# Slave.net
KiCad netlist of a schematic drawn in EAGLE
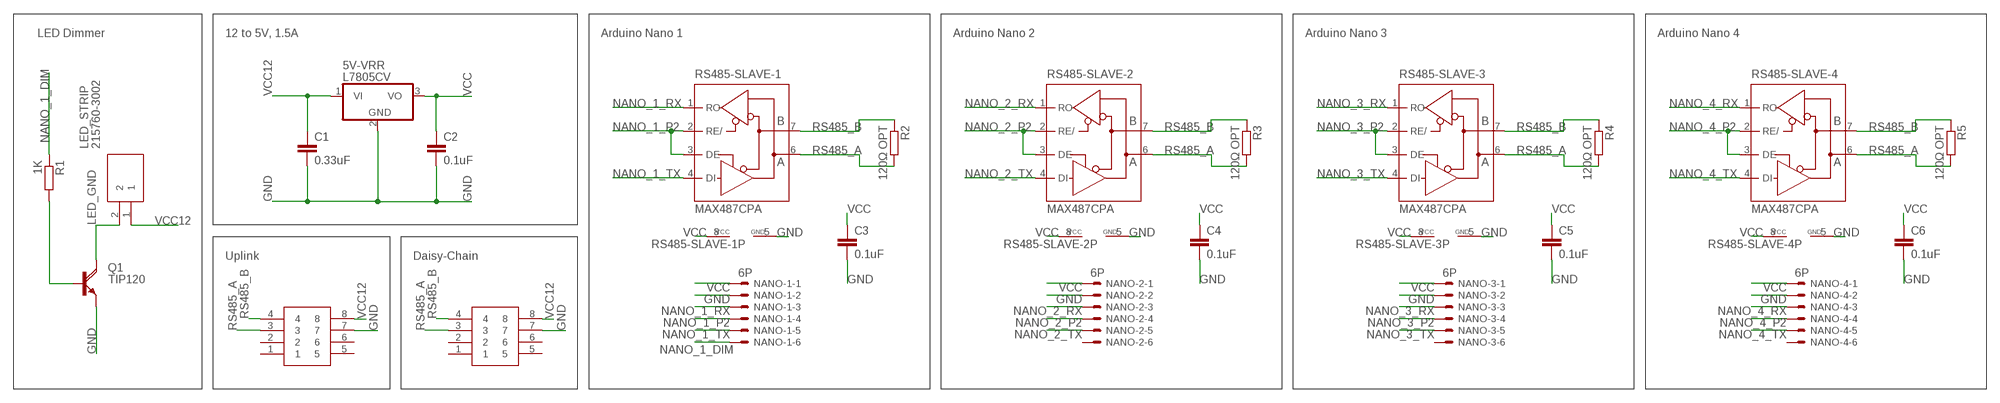
[diagram p0: schematic, sheet 1]

(export (version "E")
  (design (tool "Eeschema 10.0.6"))
  (components
    (comp (ref "5V-VRR")
      (value "L7805CV")
      (footprint "eagle-import:TO220H")
      (libsource (lib "eagle-import") (part "78T05"))
    )
    (comp (ref "C1")
      (value "0.33uF")
      (footprint "eagle-import:C025-025X050")
      (libsource (lib "eagle-import") (part "C-EU025-025X050"))
    )
    (comp (ref "C2")
      (value "0.1uF")
      (footprint "eagle-import:C025-025X050")
      (libsource (lib "eagle-import") (part "C-EU025-025X050"))
    )
    (comp (ref "C3")
      (value "0.1uF")
      (footprint "eagle-import:C025-025X050")
      (libsource (lib "eagle-import") (part "C-EU025-025X050"))
    )
    (comp (ref "C4")
      (value "0.1uF")
      (footprint "eagle-import:C025-025X050")
      (libsource (lib "eagle-import") (part "C-EU025-025X050"))
    )
    (comp (ref "C5")
      (value "0.1uF")
      (footprint "eagle-import:C025-025X050")
      (libsource (lib "eagle-import") (part "C-EU025-025X050"))
    )
    (comp (ref "C6")
      (value "0.1uF")
      (footprint "eagle-import:C025-025X050")
      (libsource (lib "eagle-import") (part "C-EU025-025X050"))
    )
    (comp (ref "LED_STRIP")
      (value "215760-3002")
      (footprint "eagle-import:215760-YY02")
      (fields (field (name "MOUSER_PART_NUMBER") "538-215760-3002"))
      (libsource (lib "eagle-import") (part "215760-3002"))
    )
    (comp (ref "NANO-1")
      (value "6P")
      (footprint "eagle-import:22-23-2061")
      (fields (field (name "MF") "MOLEX") (field (name "MPN") "22-23-2061"))
      (libsource (lib "eagle-import") (part "22-23-2061"))
    )
    (comp (ref "NANO-2")
      (value "6P")
      (footprint "eagle-import:22-23-2061")
      (fields (field (name "MF") "MOLEX") (field (name "MPN") "22-23-2061"))
      (libsource (lib "eagle-import") (part "22-23-2061"))
    )
    (comp (ref "NANO-3")
      (value "6P")
      (footprint "eagle-import:22-23-2061")
      (fields (field (name "MF") "MOLEX") (field (name "MPN") "22-23-2061"))
      (libsource (lib "eagle-import") (part "22-23-2061"))
    )
    (comp (ref "NANO-4")
      (value "6P")
      (footprint "eagle-import:22-23-2061")
      (fields (field (name "MF") "MOLEX") (field (name "MPN") "22-23-2061"))
      (libsource (lib "eagle-import") (part "22-23-2061"))
    )
    (comp (ref "Q1")
      (value "TIP120")
      (footprint "eagle-import:TO220AH")
      (libsource (lib "eagle-import") (part "TIP120"))
    )
    (comp (ref "R1")
      (value "1K")
      (footprint "eagle-import:0207_10")
      (libsource (lib "eagle-import") (part "R-EU_0207/10"))
    )
    (comp (ref "R2")
      (value "120Ω OPT")
      (footprint "eagle-import:0207_10")
      (libsource (lib "eagle-import") (part "R-EU_0207/10"))
    )
    (comp (ref "R3")
      (value "120Ω OPT")
      (footprint "eagle-import:0207_10")
      (libsource (lib "eagle-import") (part "R-EU_0207/10"))
    )
    (comp (ref "R4")
      (value "120Ω OPT")
      (footprint "eagle-import:0207_10")
      (libsource (lib "eagle-import") (part "R-EU_0207/10"))
    )
    (comp (ref "R5")
      (value "120Ω OPT")
      (footprint "eagle-import:0207_10")
      (libsource (lib "eagle-import") (part "R-EU_0207/10"))
    )
    (comp (ref "RS485-SLAVE-1")
      (value "MAX487CPA")
      (footprint "eagle-import:DIL08")
      (libsource (lib "eagle-import") (part "MAX487CPA"))
    )
    (comp (ref "RS485-SLAVE-2")
      (value "MAX487CPA")
      (footprint "eagle-import:DIL08")
      (libsource (lib "eagle-import") (part "MAX487CPA"))
    )
    (comp (ref "RS485-SLAVE-3")
      (value "MAX487CPA")
      (footprint "eagle-import:DIL08")
      (libsource (lib "eagle-import") (part "MAX487CPA"))
    )
    (comp (ref "RS485-SLAVE-4")
      (value "MAX487CPA")
      (footprint "eagle-import:DIL08")
      (libsource (lib "eagle-import") (part "MAX487CPA"))
    )
    (comp (ref "UPLINK")
      (value "212528-0801")
      (footprint "eagle-import:212528-08YY")
      (fields (field (name "MOUSER_PART_NUMBER") "538-212528-0801"))
      (libsource (lib "eagle-import") (part "212528-0801"))
    )
    (comp (ref "UPLINK1")
      (value "212528-0801")
      (footprint "eagle-import:212528-08YY")
      (fields (field (name "MOUSER_PART_NUMBER") "538-212528-0801"))
      (libsource (lib "eagle-import") (part "212528-0801"))
    )
  )
  (nets
    (net (code "1") (name "/GND") (class "Default")
      (node (ref "5V-VRR") (pin "2") (pinfunction "GND_2") (pintype "passive"))
      (node (ref "C1") (pin "2") (pinfunction "2_2") (pintype "passive"))
      (node (ref "C2") (pin "2") (pinfunction "2_2") (pintype "passive"))
      (node (ref "C3") (pin "2") (pinfunction "2_2") (pintype "passive"))
      (node (ref "C4") (pin "2") (pinfunction "2_2") (pintype "passive"))
      (node (ref "C5") (pin "2") (pinfunction "2_2") (pintype "passive"))
      (node (ref "C6") (pin "2") (pinfunction "2_2") (pintype "passive"))
      (node (ref "NANO-1") (pin "2") (pinfunction "S_2") (pintype "passive"))
      (node (ref "NANO-2") (pin "2") (pinfunction "S_2") (pintype "passive"))
      (node (ref "NANO-3") (pin "2") (pinfunction "S_2") (pintype "passive"))
      (node (ref "NANO-4") (pin "2") (pinfunction "S_2") (pintype "passive"))
      (node (ref "Q1") (pin "E") (pinfunction "E_E") (pintype "passive"))
      (node (ref "RS485-SLAVE-1") (pin "5") (pinfunction "GND_5") (pintype "power_in"))
      (node (ref "RS485-SLAVE-2") (pin "5") (pinfunction "GND_5") (pintype "power_in"))
      (node (ref "RS485-SLAVE-3") (pin "5") (pinfunction "GND_5") (pintype "power_in"))
      (node (ref "RS485-SLAVE-4") (pin "5") (pinfunction "GND_5") (pintype "power_in"))
      (node (ref "UPLINK") (pin "7") (pinfunction "7_7") (pintype "bidirectional"))
      (node (ref "UPLINK1") (pin "7") (pinfunction "7_7") (pintype "bidirectional"))
    )
    (net (code "2") (name "/LED_GND") (class "Default")
      (node (ref "LED_STRIP") (pin "2") (pinfunction "2_2") (pintype "bidirectional"))
      (node (ref "Q1") (pin "C") (pinfunction "C_C") (pintype "passive"))
    )
    (net (code "3") (name "/NANO_1_DIM") (class "Default")
      (node (ref "NANO-1") (pin "6") (pinfunction "S_6") (pintype "passive"))
      (node (ref "R1") (pin "1") (pinfunction "1_1") (pintype "passive"))
    )
    (net (code "4") (name "/NANO_1_P2") (class "Default")
      (node (ref "NANO-1") (pin "4") (pinfunction "S_4") (pintype "passive"))
      (node (ref "RS485-SLAVE-1") (pin "2") (pinfunction "RE/_2") (pintype "input"))
      (node (ref "RS485-SLAVE-1") (pin "3") (pinfunction "DE_3") (pintype "input"))
    )
    (net (code "5") (name "/NANO_1_RX") (class "Default")
      (node (ref "NANO-1") (pin "3") (pinfunction "S_3") (pintype "passive"))
      (node (ref "RS485-SLAVE-1") (pin "1") (pinfunction "RO_1") (pintype "output"))
    )
    (net (code "6") (name "/NANO_1_TX") (class "Default")
      (node (ref "NANO-1") (pin "5") (pinfunction "S_5") (pintype "passive"))
      (node (ref "RS485-SLAVE-1") (pin "4") (pinfunction "DI_4") (pintype "input"))
    )
    (net (code "7") (name "/NANO_2_P2") (class "Default")
      (node (ref "NANO-2") (pin "4") (pinfunction "S_4") (pintype "passive"))
      (node (ref "RS485-SLAVE-2") (pin "2") (pinfunction "RE/_2") (pintype "input"))
      (node (ref "RS485-SLAVE-2") (pin "3") (pinfunction "DE_3") (pintype "input"))
    )
    (net (code "8") (name "/NANO_2_RX") (class "Default")
      (node (ref "NANO-2") (pin "3") (pinfunction "S_3") (pintype "passive"))
      (node (ref "RS485-SLAVE-2") (pin "1") (pinfunction "RO_1") (pintype "output"))
    )
    (net (code "9") (name "/NANO_2_TX") (class "Default")
      (node (ref "NANO-2") (pin "5") (pinfunction "S_5") (pintype "passive"))
      (node (ref "RS485-SLAVE-2") (pin "4") (pinfunction "DI_4") (pintype "input"))
    )
    (net (code "10") (name "/NANO_3_P2") (class "Default")
      (node (ref "NANO-3") (pin "4") (pinfunction "S_4") (pintype "passive"))
      (node (ref "RS485-SLAVE-3") (pin "2") (pinfunction "RE/_2") (pintype "input"))
      (node (ref "RS485-SLAVE-3") (pin "3") (pinfunction "DE_3") (pintype "input"))
    )
    (net (code "11") (name "/NANO_3_RX") (class "Default")
      (node (ref "NANO-3") (pin "3") (pinfunction "S_3") (pintype "passive"))
      (node (ref "RS485-SLAVE-3") (pin "1") (pinfunction "RO_1") (pintype "output"))
    )
    (net (code "12") (name "/NANO_3_TX") (class "Default")
      (node (ref "NANO-3") (pin "5") (pinfunction "S_5") (pintype "passive"))
      (node (ref "RS485-SLAVE-3") (pin "4") (pinfunction "DI_4") (pintype "input"))
    )
    (net (code "13") (name "/NANO_4_P2") (class "Default")
      (node (ref "NANO-4") (pin "4") (pinfunction "S_4") (pintype "passive"))
      (node (ref "RS485-SLAVE-4") (pin "2") (pinfunction "RE/_2") (pintype "input"))
      (node (ref "RS485-SLAVE-4") (pin "3") (pinfunction "DE_3") (pintype "input"))
    )
    (net (code "14") (name "/NANO_4_RX") (class "Default")
      (node (ref "NANO-4") (pin "3") (pinfunction "S_3") (pintype "passive"))
      (node (ref "RS485-SLAVE-4") (pin "1") (pinfunction "RO_1") (pintype "output"))
    )
    (net (code "15") (name "/NANO_4_TX") (class "Default")
      (node (ref "NANO-4") (pin "5") (pinfunction "S_5") (pintype "passive"))
      (node (ref "RS485-SLAVE-4") (pin "4") (pinfunction "DI_4") (pintype "input"))
    )
    (net (code "16") (name "/RS485_A") (class "Default")
      (node (ref "R2") (pin "2") (pinfunction "2_2") (pintype "passive"))
      (node (ref "R3") (pin "2") (pinfunction "2_2") (pintype "passive"))
      (node (ref "R4") (pin "2") (pinfunction "2_2") (pintype "passive"))
      (node (ref "R5") (pin "2") (pinfunction "2_2") (pintype "passive"))
      (node (ref "RS485-SLAVE-1") (pin "6") (pinfunction "A_6") (pintype "passive"))
      (node (ref "RS485-SLAVE-2") (pin "6") (pinfunction "A_6") (pintype "passive"))
      (node (ref "RS485-SLAVE-3") (pin "6") (pinfunction "A_6") (pintype "passive"))
      (node (ref "RS485-SLAVE-4") (pin "6") (pinfunction "A_6") (pintype "passive"))
      (node (ref "UPLINK") (pin "3") (pinfunction "3_3") (pintype "bidirectional"))
      (node (ref "UPLINK1") (pin "3") (pinfunction "3_3") (pintype "bidirectional"))
    )
    (net (code "17") (name "/RS485_B") (class "Default")
      (node (ref "R2") (pin "1") (pinfunction "1_1") (pintype "passive"))
      (node (ref "R3") (pin "1") (pinfunction "1_1") (pintype "passive"))
      (node (ref "R4") (pin "1") (pinfunction "1_1") (pintype "passive"))
      (node (ref "R5") (pin "1") (pinfunction "1_1") (pintype "passive"))
      (node (ref "RS485-SLAVE-1") (pin "7") (pinfunction "B_7") (pintype "passive"))
      (node (ref "RS485-SLAVE-2") (pin "7") (pinfunction "B_7") (pintype "passive"))
      (node (ref "RS485-SLAVE-3") (pin "7") (pinfunction "B_7") (pintype "passive"))
      (node (ref "RS485-SLAVE-4") (pin "7") (pinfunction "B_7") (pintype "passive"))
      (node (ref "UPLINK") (pin "4") (pinfunction "4_4") (pintype "bidirectional"))
      (node (ref "UPLINK1") (pin "4") (pinfunction "4_4") (pintype "bidirectional"))
    )
    (net (code "18") (name "/VCC") (class "Default")
      (node (ref "5V-VRR") (pin "3") (pinfunction "VO_3") (pintype "passive"))
      (node (ref "C2") (pin "1") (pinfunction "1_1") (pintype "passive"))
      (node (ref "C3") (pin "1") (pinfunction "1_1") (pintype "passive"))
      (node (ref "C4") (pin "1") (pinfunction "1_1") (pintype "passive"))
      (node (ref "C5") (pin "1") (pinfunction "1_1") (pintype "passive"))
      (node (ref "C6") (pin "1") (pinfunction "1_1") (pintype "passive"))
      (node (ref "NANO-1") (pin "1") (pinfunction "S_1") (pintype "passive"))
      (node (ref "NANO-2") (pin "1") (pinfunction "S_1") (pintype "passive"))
      (node (ref "NANO-3") (pin "1") (pinfunction "S_1") (pintype "passive"))
      (node (ref "NANO-4") (pin "1") (pinfunction "S_1") (pintype "passive"))
      (node (ref "RS485-SLAVE-1") (pin "8") (pinfunction "VCC_8") (pintype "power_in"))
      (node (ref "RS485-SLAVE-2") (pin "8") (pinfunction "VCC_8") (pintype "power_in"))
      (node (ref "RS485-SLAVE-3") (pin "8") (pinfunction "VCC_8") (pintype "power_in"))
      (node (ref "RS485-SLAVE-4") (pin "8") (pinfunction "VCC_8") (pintype "power_in"))
    )
    (net (code "19") (name "/VCC12") (class "Default")
      (node (ref "5V-VRR") (pin "1") (pinfunction "VI_1") (pintype "input"))
      (node (ref "C1") (pin "1") (pinfunction "1_1") (pintype "passive"))
      (node (ref "LED_STRIP") (pin "1") (pinfunction "1_1") (pintype "bidirectional"))
      (node (ref "UPLINK") (pin "8") (pinfunction "8_8") (pintype "bidirectional"))
      (node (ref "UPLINK1") (pin "8") (pinfunction "8_8") (pintype "bidirectional"))
    )
    (net (code "20") (name "Net-(Q1-PadB)") (class "Default")
      (node (ref "Q1") (pin "B") (pinfunction "B_B") (pintype "passive"))
      (node (ref "R1") (pin "2") (pinfunction "2_2") (pintype "passive"))
    )
    (net (code "21") (name "unconnected-(NANO-2F-S-Pad6)") (class "Default")
      (node (ref "NANO-2") (pin "6") (pinfunction "S_6") (pintype "passive"))
    )
    (net (code "22") (name "unconnected-(NANO-3F-S-Pad6)") (class "Default")
      (node (ref "NANO-3") (pin "6") (pinfunction "S_6") (pintype "passive"))
    )
    (net (code "23") (name "unconnected-(NANO-4F-S-Pad6)") (class "Default")
      (node (ref "NANO-4") (pin "6") (pinfunction "S_6") (pintype "passive"))
    )
    (net (code "24") (name "unconnected-(UPLINK-Pad1)") (class "Default")
      (node (ref "UPLINK") (pin "1") (pinfunction "1_1") (pintype "bidirectional"))
    )
    (net (code "25") (name "unconnected-(UPLINK-Pad2)") (class "Default")
      (node (ref "UPLINK") (pin "2") (pinfunction "2_2") (pintype "bidirectional"))
    )
    (net (code "26") (name "unconnected-(UPLINK-Pad5)") (class "Default")
      (node (ref "UPLINK") (pin "5") (pinfunction "5_5") (pintype "bidirectional"))
    )
    (net (code "27") (name "unconnected-(UPLINK-Pad6)") (class "Default")
      (node (ref "UPLINK") (pin "6") (pinfunction "6_6") (pintype "bidirectional"))
    )
    (net (code "28") (name "unconnected-(UPLINK1-Pad1)") (class "Default")
      (node (ref "UPLINK1") (pin "1") (pinfunction "1_1") (pintype "bidirectional"))
    )
    (net (code "29") (name "unconnected-(UPLINK1-Pad2)") (class "Default")
      (node (ref "UPLINK1") (pin "2") (pinfunction "2_2") (pintype "bidirectional"))
    )
    (net (code "30") (name "unconnected-(UPLINK1-Pad5)") (class "Default")
      (node (ref "UPLINK1") (pin "5") (pinfunction "5_5") (pintype "bidirectional"))
    )
    (net (code "31") (name "unconnected-(UPLINK1-Pad6)") (class "Default")
      (node (ref "UPLINK1") (pin "6") (pinfunction "6_6") (pintype "bidirectional"))
    )
  )
)
